# toolbox.net
KiCad netlist of a schematic drawn in EAGLE
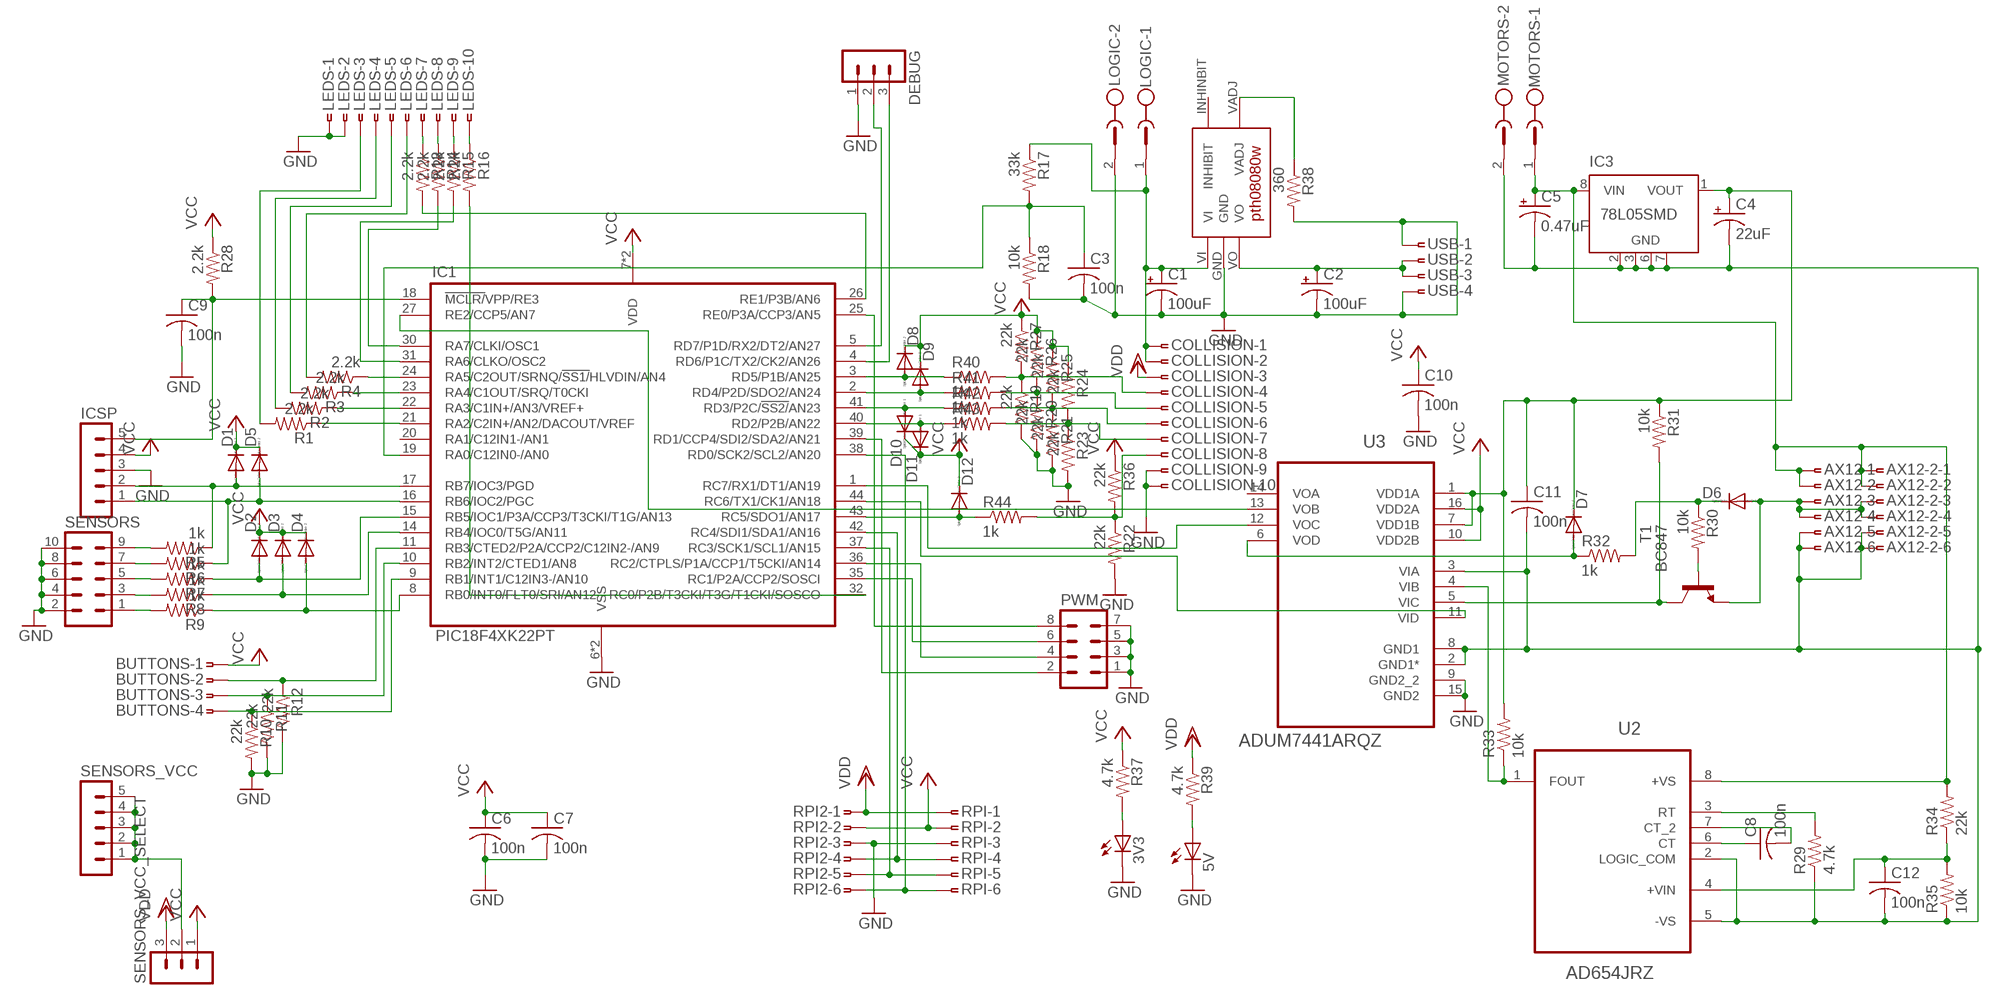
[diagram p0: schematic, sheet 1]

(export (version "E")
  (design (tool "Eeschema 10.0.6"))
  (components
    (comp (ref "3V3")
      (value "LEDCHIPLED_0805")
      (footprint "eagle-import:CHIPLED_0805")
      (libsource (lib "eagle-import") (part "LEDCHIPLED_0805"))
    )
    (comp (ref "5V")
      (value "LEDCHIPLED_0805")
      (footprint "eagle-import:CHIPLED_0805")
      (libsource (lib "eagle-import") (part "LEDCHIPLED_0805"))
    )
    (comp (ref "AX12")
      (value "SMDTOP-6")
      (footprint "eagle-import:SMDTOP6")
      (libsource (lib "eagle-import") (part "SMDTOP-6"))
    )
    (comp (ref "AX12-2")
      (value "SMDTOP-6")
      (footprint "eagle-import:SMDTOP6")
      (libsource (lib "eagle-import") (part "SMDTOP-6"))
    )
    (comp (ref "BUTTONS")
      (value "SMDTOP-4")
      (footprint "eagle-import:SMDTOP4")
      (libsource (lib "eagle-import") (part "SMDTOP-4"))
    )
    (comp (ref "C1")
      (value "100uF")
      (footprint "eagle-import:E2,5-6E")
      (libsource (lib "eagle-import") (part "CPOL-USE2,5-6E"))
    )
    (comp (ref "C2")
      (value "100uF")
      (footprint "eagle-import:E2,5-6E")
      (libsource (lib "eagle-import") (part "CPOL-USE2,5-6E"))
    )
    (comp (ref "C3")
      (value "100n")
      (footprint "eagle-import:C0805")
      (libsource (lib "eagle-import") (part "C-USC0805"))
    )
    (comp (ref "C4")
      (value "22uF")
      (footprint "eagle-import:E2-5")
      (libsource (lib "eagle-import") (part "CPOL-USE2-5"))
    )
    (comp (ref "C5")
      (value "0.47uF")
      (footprint "eagle-import:E2-5")
      (libsource (lib "eagle-import") (part "CPOL-USE2-5"))
    )
    (comp (ref "C6")
      (value "100n")
      (footprint "eagle-import:C0805")
      (libsource (lib "eagle-import") (part "C-USC0805"))
    )
    (comp (ref "C7")
      (value "100n")
      (footprint "eagle-import:C0805")
      (libsource (lib "eagle-import") (part "C-USC0805"))
    )
    (comp (ref "C8")
      (value "100n")
      (footprint "eagle-import:C0805")
      (libsource (lib "eagle-import") (part "C-USC0805"))
    )
    (comp (ref "C9")
      (value "100n")
      (footprint "eagle-import:C0805")
      (libsource (lib "eagle-import") (part "C-USC0805"))
    )
    (comp (ref "C10")
      (value "100n")
      (footprint "eagle-import:C0805")
      (libsource (lib "eagle-import") (part "C-USC0805"))
    )
    (comp (ref "C11")
      (value "100n")
      (footprint "eagle-import:C0805")
      (libsource (lib "eagle-import") (part "C-USC0805"))
    )
    (comp (ref "C12")
      (value "100n")
      (footprint "eagle-import:C0805")
      (libsource (lib "eagle-import") (part "C-USC0805"))
    )
    (comp (ref "COLLISION")
      (value "SMDTOP-10")
      (footprint "eagle-import:SMDTOP10")
      (libsource (lib "eagle-import") (part "SMDTOP-10"))
    )
    (comp (ref "D1")
      (value "DIODE-SOD523")
      (footprint "eagle-import:SOD523")
      (libsource (lib "eagle-import") (part "DIODE-SOD523"))
    )
    (comp (ref "D2")
      (value "DIODE-SOD523")
      (footprint "eagle-import:SOD523")
      (libsource (lib "eagle-import") (part "DIODE-SOD523"))
    )
    (comp (ref "D3")
      (value "DIODE-SOD523")
      (footprint "eagle-import:SOD523")
      (libsource (lib "eagle-import") (part "DIODE-SOD523"))
    )
    (comp (ref "D4")
      (value "DIODE-SOD523")
      (footprint "eagle-import:SOD523")
      (libsource (lib "eagle-import") (part "DIODE-SOD523"))
    )
    (comp (ref "D5")
      (value "DIODE-SOD523")
      (footprint "eagle-import:SOD523")
      (libsource (lib "eagle-import") (part "DIODE-SOD523"))
    )
    (comp (ref "D6")
      (value "DIODE-SOD523")
      (footprint "eagle-import:SOD523")
      (libsource (lib "eagle-import") (part "DIODE-SOD523"))
    )
    (comp (ref "D7")
      (value "DIODE-SOD523")
      (footprint "eagle-import:SOD523")
      (libsource (lib "eagle-import") (part "DIODE-SOD523"))
    )
    (comp (ref "D8")
      (value "DIODE-SOD523")
      (footprint "eagle-import:SOD523")
      (libsource (lib "eagle-import") (part "DIODE-SOD523"))
    )
    (comp (ref "D9")
      (value "DIODE-SOD523")
      (footprint "eagle-import:SOD523")
      (libsource (lib "eagle-import") (part "DIODE-SOD523"))
    )
    (comp (ref "D10")
      (value "DIODE-SOD523")
      (footprint "eagle-import:SOD523")
      (libsource (lib "eagle-import") (part "DIODE-SOD523"))
    )
    (comp (ref "D11")
      (value "DIODE-SOD523")
      (footprint "eagle-import:SOD523")
      (libsource (lib "eagle-import") (part "DIODE-SOD523"))
    )
    (comp (ref "D12")
      (value "DIODE-SOD523")
      (footprint "eagle-import:SOD523")
      (libsource (lib "eagle-import") (part "DIODE-SOD523"))
    )
    (comp (ref "DEBUG")
      (value "MA03-1")
      (footprint "eagle-import:MA03-1")
      (libsource (lib "eagle-import") (part "MA03-1"))
    )
    (comp (ref "IC1")
      (value "PIC18F4XK22PT")
      (footprint "eagle-import:TQFP44")
      (libsource (lib "eagle-import") (part "PIC18F4XK22PT"))
    )
    (comp (ref "IC3")
      (value "78L05SMD")
      (footprint "eagle-import:SO08")
      (libsource (lib "eagle-import") (part "78LSMD05"))
    )
    (comp (ref "ICSP")
      (value "MA05-1")
      (footprint "eagle-import:MA05-1")
      (libsource (lib "eagle-import") (part "MA05-1"))
    )
    (comp (ref "LEDS")
      (value "SMDTOP-10")
      (footprint "eagle-import:SMDTOP10")
      (libsource (lib "eagle-import") (part "SMDTOP-10"))
    )
    (comp (ref "LOGIC")
      (value "MSTBV2")
      (footprint "eagle-import:MSTBV2")
      (libsource (lib "eagle-import") (part "MSTBV2"))
    )
    (comp (ref "MOTORS")
      (value "MSTBV2")
      (footprint "eagle-import:MSTBV2")
      (libsource (lib "eagle-import") (part "MSTBV2"))
    )
    (comp (ref "PWM")
      (value "MA04-2")
      (footprint "eagle-import:MA04-2")
      (libsource (lib "eagle-import") (part "MA04-2"))
    )
    (comp (ref "R1")
      (value "2.2k")
      (footprint "eagle-import:M0805")
      (libsource (lib "eagle-import") (part "R-US_M0805"))
    )
    (comp (ref "R2")
      (value "2.2k")
      (footprint "eagle-import:M0805")
      (libsource (lib "eagle-import") (part "R-US_M0805"))
    )
    (comp (ref "R3")
      (value "2.2k")
      (footprint "eagle-import:M0805")
      (libsource (lib "eagle-import") (part "R-US_M0805"))
    )
    (comp (ref "R4")
      (value "2.2k")
      (footprint "eagle-import:M0805")
      (libsource (lib "eagle-import") (part "R-US_M0805"))
    )
    (comp (ref "R5")
      (value "1k")
      (footprint "eagle-import:M0805")
      (libsource (lib "eagle-import") (part "R-US_M0805"))
    )
    (comp (ref "R6")
      (value "1k")
      (footprint "eagle-import:M0805")
      (libsource (lib "eagle-import") (part "R-US_M0805"))
    )
    (comp (ref "R7")
      (value "1k")
      (footprint "eagle-import:M0805")
      (libsource (lib "eagle-import") (part "R-US_M0805"))
    )
    (comp (ref "R8")
      (value "1k")
      (footprint "eagle-import:M0805")
      (libsource (lib "eagle-import") (part "R-US_M0805"))
    )
    (comp (ref "R9")
      (value "1k")
      (footprint "eagle-import:M0805")
      (libsource (lib "eagle-import") (part "R-US_M0805"))
    )
    (comp (ref "R10")
      (value "22k")
      (footprint "eagle-import:M0805")
      (libsource (lib "eagle-import") (part "R-US_M0805"))
    )
    (comp (ref "R11")
      (value "22k")
      (footprint "eagle-import:M0805")
      (libsource (lib "eagle-import") (part "R-US_M0805"))
    )
    (comp (ref "R12")
      (value "22k")
      (footprint "eagle-import:M0805")
      (libsource (lib "eagle-import") (part "R-US_M0805"))
    )
    (comp (ref "R13")
      (value "2.2k")
      (footprint "eagle-import:M0805")
      (libsource (lib "eagle-import") (part "R-US_M0805"))
    )
    (comp (ref "R14")
      (value "2.2k")
      (footprint "eagle-import:M0805")
      (libsource (lib "eagle-import") (part "R-US_M0805"))
    )
    (comp (ref "R15")
      (value "2.2k")
      (footprint "eagle-import:M0805")
      (libsource (lib "eagle-import") (part "R-US_M0805"))
    )
    (comp (ref "R16")
      (value "2.2k")
      (footprint "eagle-import:M0805")
      (libsource (lib "eagle-import") (part "R-US_M0805"))
    )
    (comp (ref "R17")
      (value "33k")
      (footprint "eagle-import:M0805")
      (libsource (lib "eagle-import") (part "R-US_M0805"))
    )
    (comp (ref "R18")
      (value "10k")
      (footprint "eagle-import:M0805")
      (libsource (lib "eagle-import") (part "R-US_M0805"))
    )
    (comp (ref "R19")
      (value "22k")
      (footprint "eagle-import:M0805")
      (libsource (lib "eagle-import") (part "R-US_M0805"))
    )
    (comp (ref "R20")
      (value "22k")
      (footprint "eagle-import:M0805")
      (libsource (lib "eagle-import") (part "R-US_M0805"))
    )
    (comp (ref "R21")
      (value "22k")
      (footprint "eagle-import:M0805")
      (libsource (lib "eagle-import") (part "R-US_M0805"))
    )
    (comp (ref "R22")
      (value "22k")
      (footprint "eagle-import:M0805")
      (libsource (lib "eagle-import") (part "R-US_M0805"))
    )
    (comp (ref "R23")
      (value "22k")
      (footprint "eagle-import:M0805")
      (libsource (lib "eagle-import") (part "R-US_M0805"))
    )
    (comp (ref "R24")
      (value "22k")
      (footprint "eagle-import:M0805")
      (libsource (lib "eagle-import") (part "R-US_M0805"))
    )
    (comp (ref "R25")
      (value "22k")
      (footprint "eagle-import:M0805")
      (libsource (lib "eagle-import") (part "R-US_M0805"))
    )
    (comp (ref "R26")
      (value "22k")
      (footprint "eagle-import:M0805")
      (libsource (lib "eagle-import") (part "R-US_M0805"))
    )
    (comp (ref "R27")
      (value "22k")
      (footprint "eagle-import:M0805")
      (libsource (lib "eagle-import") (part "R-US_M0805"))
    )
    (comp (ref "R28")
      (value "2.2k")
      (footprint "eagle-import:M0805")
      (libsource (lib "eagle-import") (part "R-US_M0805"))
    )
    (comp (ref "R29")
      (value "4.7k")
      (footprint "eagle-import:M0805")
      (libsource (lib "eagle-import") (part "R-US_M0805"))
    )
    (comp (ref "R30")
      (value "10k")
      (footprint "eagle-import:M0805")
      (libsource (lib "eagle-import") (part "R-US_M0805"))
    )
    (comp (ref "R31")
      (value "10k")
      (footprint "eagle-import:M0805")
      (libsource (lib "eagle-import") (part "R-US_M0805"))
    )
    (comp (ref "R32")
      (value "1k")
      (footprint "eagle-import:M0805")
      (libsource (lib "eagle-import") (part "R-US_M0805"))
    )
    (comp (ref "R33")
      (value "10k")
      (footprint "eagle-import:M0805")
      (libsource (lib "eagle-import") (part "R-US_M0805"))
    )
    (comp (ref "R34")
      (value "22k")
      (footprint "eagle-import:M0805")
      (libsource (lib "eagle-import") (part "R-US_M0805"))
    )
    (comp (ref "R35")
      (value "10k")
      (footprint "eagle-import:M0805")
      (libsource (lib "eagle-import") (part "R-US_M0805"))
    )
    (comp (ref "R36")
      (value "22k")
      (footprint "eagle-import:M0805")
      (libsource (lib "eagle-import") (part "R-US_M0805"))
    )
    (comp (ref "R37")
      (value "4.7k")
      (footprint "eagle-import:M0805")
      (libsource (lib "eagle-import") (part "R-US_M0805"))
    )
    (comp (ref "R38")
      (value "360")
      (footprint "eagle-import:M0805")
      (libsource (lib "eagle-import") (part "R-US_M0805"))
    )
    (comp (ref "R39")
      (value "4.7k")
      (footprint "eagle-import:M0805")
      (libsource (lib "eagle-import") (part "R-US_M0805"))
    )
    (comp (ref "R40")
      (value "1k")
      (footprint "eagle-import:M0805")
      (libsource (lib "eagle-import") (part "R-US_M0805"))
    )
    (comp (ref "R41")
      (value "1k")
      (footprint "eagle-import:M0805")
      (libsource (lib "eagle-import") (part "R-US_M0805"))
    )
    (comp (ref "R42")
      (value "1k")
      (footprint "eagle-import:M0805")
      (libsource (lib "eagle-import") (part "R-US_M0805"))
    )
    (comp (ref "R43")
      (value "1k")
      (footprint "eagle-import:M0805")
      (libsource (lib "eagle-import") (part "R-US_M0805"))
    )
    (comp (ref "R44")
      (value "1k")
      (footprint "eagle-import:M0805")
      (libsource (lib "eagle-import") (part "R-US_M0805"))
    )
    (comp (ref "RPI")
      (value "SMDTOP-6")
      (footprint "eagle-import:SMDTOP6")
      (libsource (lib "eagle-import") (part "SMDTOP-6"))
    )
    (comp (ref "RPI2")
      (value "SMDTOP-6")
      (footprint "eagle-import:SMDTOP6")
      (libsource (lib "eagle-import") (part "SMDTOP-6"))
    )
    (comp (ref "SENSORS")
      (value "MA05-2")
      (footprint "eagle-import:MA05-2")
      (libsource (lib "eagle-import") (part "MA05-2"))
    )
    (comp (ref "SENSORS_VCC")
      (value "MA05-1")
      (footprint "eagle-import:MA05-1")
      (libsource (lib "eagle-import") (part "MA05-1"))
    )
    (comp (ref "SENSORS_VCC_SELECT")
      (value "MA03-1")
      (footprint "eagle-import:MA03-1")
      (libsource (lib "eagle-import") (part "MA03-1"))
    )
    (comp (ref "T1")
      (value "BC847")
      (footprint "eagle-import:SOT23")
      (libsource (lib "eagle-import") (part "BC847"))
    )
    (comp (ref "U$1")
      (value "REGUL_PTH")
      (footprint "eagle-import:REGUL_PTH")
      (libsource (lib "eagle-import") (part "REGUL_PTH"))
    )
    (comp (ref "U2")
      (value "AD654JRZ")
      (footprint "eagle-import:SOIC127P600X175-8N")
      (libsource (lib "eagle-import") (part "AD654JRZ"))
    )
    (comp (ref "U3")
      (value "ADUM7441ARQZ")
      (footprint "eagle-import:SOP64P600X175-16N")
      (libsource (lib "eagle-import") (part "ADUM7441ARQZ"))
    )
    (comp (ref "USB")
      (value "SMDTOP-4")
      (footprint "eagle-import:SMDTOP4")
      (libsource (lib "eagle-import") (part "SMDTOP-4"))
    )
  )
  (nets
    (net (code "1") (name "GND") (class "Default")
      (node (ref "3V3") (pin "C") (pinfunction "C_C") (pintype "passive"))
      (node (ref "5V") (pin "C") (pinfunction "C_C") (pintype "passive"))
      (node (ref "C1") (pin "-") (pinfunction "-_-") (pintype "passive"))
      (node (ref "C10") (pin "2") (pinfunction "2_2") (pintype "passive"))
      (node (ref "C2") (pin "-") (pinfunction "-_-") (pintype "passive"))
      (node (ref "C3") (pin "2") (pinfunction "2_2") (pintype "passive"))
      (node (ref "C6") (pin "2") (pinfunction "2_2") (pintype "passive"))
      (node (ref "C7") (pin "2") (pinfunction "2_2") (pintype "passive"))
      (node (ref "C9") (pin "2") (pinfunction "2_2") (pintype "passive"))
      (node (ref "COLLISION") (pin "10") (pinfunction "1_10") (pintype "passive"))
      (node (ref "COLLISION") (pin "9") (pinfunction "1_9") (pintype "passive"))
      (node (ref "DEBUG") (pin "1") (pinfunction "1_1") (pintype "passive"))
      (node (ref "IC1") (pin "29") (pinfunction "VSS_29") (pintype "power_in"))
      (node (ref "IC1") (pin "6") (pinfunction "VSS_6") (pintype "power_in"))
      (node (ref "ICSP") (pin "3") (pinfunction "3_3") (pintype "passive"))
      (node (ref "LEDS") (pin "1") (pinfunction "1_1") (pintype "passive"))
      (node (ref "LEDS") (pin "2") (pinfunction "1_2") (pintype "passive"))
      (node (ref "LOGIC") (pin "2") (pinfunction "SK_2") (pintype "passive"))
      (node (ref "PWM") (pin "1") (pinfunction "1_1") (pintype "passive"))
      (node (ref "PWM") (pin "3") (pinfunction "3_3") (pintype "passive"))
      (node (ref "PWM") (pin "5") (pinfunction "5_5") (pintype "passive"))
      (node (ref "PWM") (pin "7") (pinfunction "7_7") (pintype "passive"))
      (node (ref "R10") (pin "2") (pinfunction "2_2") (pintype "passive"))
      (node (ref "R11") (pin "2") (pinfunction "2_2") (pintype "passive"))
      (node (ref "R12") (pin "2") (pinfunction "2_2") (pintype "passive"))
      (node (ref "R18") (pin "2") (pinfunction "2_2") (pintype "passive"))
      (node (ref "R19") (pin "2") (pinfunction "2_2") (pintype "passive"))
      (node (ref "R20") (pin "2") (pinfunction "2_2") (pintype "passive"))
      (node (ref "R21") (pin "2") (pinfunction "2_2") (pintype "passive"))
      (node (ref "R22") (pin "2") (pinfunction "2_2") (pintype "passive"))
      (node (ref "R23") (pin "2") (pinfunction "2_2") (pintype "passive"))
      (node (ref "R38") (pin "2") (pinfunction "2_2") (pintype "passive"))
      (node (ref "RPI") (pin "3") (pinfunction "1_3") (pintype "passive"))
      (node (ref "RPI2") (pin "3") (pinfunction "1_3") (pintype "passive"))
      (node (ref "SENSORS") (pin "10") (pinfunction "10_10") (pintype "passive"))
      (node (ref "SENSORS") (pin "2") (pinfunction "2_2") (pintype "passive"))
      (node (ref "SENSORS") (pin "4") (pinfunction "4_4") (pintype "passive"))
      (node (ref "SENSORS") (pin "6") (pinfunction "6_6") (pintype "passive"))
      (node (ref "SENSORS") (pin "8") (pinfunction "8_8") (pintype "passive"))
      (node (ref "U$1") (pin "GND") (pinfunction "GND_GND") (pintype "bidirectional"))
      (node (ref "U3") (pin "15") (pinfunction "GND2_15") (pintype "passive"))
      (node (ref "U3") (pin "9") (pinfunction "GND2_2_9") (pintype "passive"))
      (node (ref "USB") (pin "1") (pinfunction "1_1") (pintype "passive"))
      (node (ref "USB") (pin "4") (pinfunction "1_4") (pintype "passive"))
    )
    (net (code "2") (name "Net-(3V3-PadA)") (class "Default")
      (node (ref "3V3") (pin "A") (pinfunction "A_A") (pintype "passive"))
      (node (ref "R37") (pin "2") (pinfunction "2_2") (pintype "passive"))
    )
    (net (code "3") (name "Net-(5V-PadA)") (class "Default")
      (node (ref "5V") (pin "A") (pinfunction "A_A") (pintype "passive"))
      (node (ref "R39") (pin "2") (pinfunction "2_2") (pintype "passive"))
    )
    (net (code "4") (name "Net-(AX12-2B-1)") (class "Default")
      (node (ref "AX12") (pin "1") (pinfunction "1_1") (pintype "passive"))
      (node (ref "AX12") (pin "2") (pinfunction "1_2") (pintype "passive"))
      (node (ref "AX12-2") (pin "1") (pinfunction "1_1") (pintype "passive"))
      (node (ref "AX12-2") (pin "2") (pinfunction "1_2") (pintype "passive"))
      (node (ref "C5") (pin "+") (pinfunction "+_+") (pintype "passive"))
      (node (ref "IC3") (pin "8") (pinfunction "VIN_8") (pintype "passive"))
      (node (ref "MOTORS") (pin "1") (pinfunction "SK_1") (pintype "passive"))
      (node (ref "R34") (pin "2") (pinfunction "2_2") (pintype "passive"))
      (node (ref "U2") (pin "8") (pinfunction "+VS_8") (pintype "power_in"))
    )
    (net (code "5") (name "Net-(AX12-2C-1)") (class "Default")
      (node (ref "AX12") (pin "3") (pinfunction "1_3") (pintype "passive"))
      (node (ref "AX12") (pin "4") (pinfunction "1_4") (pintype "passive"))
      (node (ref "AX12-2") (pin "3") (pinfunction "1_3") (pintype "passive"))
      (node (ref "AX12-2") (pin "4") (pinfunction "1_4") (pintype "passive"))
      (node (ref "D6") (pin "A") (pinfunction "A_A") (pintype "passive"))
      (node (ref "T1") (pin "2") (pinfunction "E_2") (pintype "passive"))
    )
    (net (code "6") (name "Net-(AX12-2E-1)") (class "Default")
      (node (ref "AX12") (pin "5") (pinfunction "1_5") (pintype "passive"))
      (node (ref "AX12") (pin "6") (pinfunction "1_6") (pintype "passive"))
      (node (ref "AX12-2") (pin "5") (pinfunction "1_5") (pintype "passive"))
      (node (ref "AX12-2") (pin "6") (pinfunction "1_6") (pintype "passive"))
      (node (ref "C11") (pin "2") (pinfunction "2_2") (pintype "passive"))
      (node (ref "C12") (pin "2") (pinfunction "2_2") (pintype "passive"))
      (node (ref "C4") (pin "-") (pinfunction "-_-") (pintype "passive"))
      (node (ref "C5") (pin "-") (pinfunction "-_-") (pintype "passive"))
      (node (ref "IC3") (pin "2") (pinfunction "GND_2") (pintype "power_in"))
      (node (ref "IC3") (pin "3") (pinfunction "GND_3") (pintype "power_in"))
      (node (ref "IC3") (pin "6") (pinfunction "GND_6") (pintype "power_in"))
      (node (ref "IC3") (pin "7") (pinfunction "GND_7") (pintype "power_in"))
      (node (ref "MOTORS") (pin "2") (pinfunction "SK_2") (pintype "passive"))
      (node (ref "R29") (pin "1") (pinfunction "1_1") (pintype "passive"))
      (node (ref "R35") (pin "1") (pinfunction "1_1") (pintype "passive"))
      (node (ref "U2") (pin "2") (pinfunction "LOGIC_COM_2") (pintype "passive"))
      (node (ref "U2") (pin "5") (pinfunction "-VS_5") (pintype "power_in"))
      (node (ref "U3") (pin "2") (pinfunction "GND1*_2") (pintype "passive"))
      (node (ref "U3") (pin "3") (pinfunction "VIA_3") (pintype "input"))
      (node (ref "U3") (pin "8") (pinfunction "GND1_8") (pintype "passive"))
    )
    (net (code "7") (name "Net-(BUTTONSB-1)") (class "Default")
      (node (ref "BUTTONS") (pin "2") (pinfunction "1_2") (pintype "passive"))
      (node (ref "IC1") (pin "11") (pinfunction "RB3/CTED2/P2A/CCP2/C12IN2-/AN9_11") (pintype "bidirectional"))
      (node (ref "R12") (pin "1") (pinfunction "1_1") (pintype "passive"))
    )
    (net (code "8") (name "Net-(BUTTONSC-1)") (class "Default")
      (node (ref "BUTTONS") (pin "3") (pinfunction "1_3") (pintype "passive"))
      (node (ref "IC1") (pin "10") (pinfunction "RB2/INT2/CTED1/AN8_10") (pintype "bidirectional"))
      (node (ref "R11") (pin "1") (pinfunction "1_1") (pintype "passive"))
    )
    (net (code "9") (name "Net-(BUTTONSD-1)") (class "Default")
      (node (ref "BUTTONS") (pin "4") (pinfunction "1_4") (pintype "passive"))
      (node (ref "IC1") (pin "9") (pinfunction "RB1/INT1/C12IN3-/AN10_9") (pintype "bidirectional"))
      (node (ref "R10") (pin "1") (pinfunction "1_1") (pintype "passive"))
    )
    (net (code "10") (name "Net-(COLLISIONC-1)") (class "Default")
      (node (ref "C1") (pin "+") (pinfunction "+_+") (pintype "passive"))
      (node (ref "COLLISION") (pin "1") (pinfunction "1_1") (pintype "passive"))
      (node (ref "COLLISION") (pin "2") (pinfunction "1_2") (pintype "passive"))
      (node (ref "LOGIC") (pin "1") (pinfunction "SK_1") (pintype "passive"))
      (node (ref "R17") (pin "1") (pinfunction "1_1") (pintype "passive"))
      (node (ref "U$1") (pin "VI") (pinfunction "VI_VI") (pintype "bidirectional"))
    )
    (net (code "11") (name "Net-(COLLISIONE-1)") (class "Default")
      (node (ref "COLLISION") (pin "4") (pinfunction "1_4") (pintype "passive"))
      (node (ref "R19") (pin "1") (pinfunction "1_1") (pintype "passive"))
      (node (ref "R27") (pin "2") (pinfunction "2_2") (pintype "passive"))
      (node (ref "R40") (pin "2") (pinfunction "2_2") (pintype "passive"))
    )
    (net (code "12") (name "Net-(COLLISIONF-1)") (class "Default")
      (node (ref "COLLISION") (pin "5") (pinfunction "1_5") (pintype "passive"))
      (node (ref "R20") (pin "1") (pinfunction "1_1") (pintype "passive"))
      (node (ref "R26") (pin "2") (pinfunction "2_2") (pintype "passive"))
      (node (ref "R41") (pin "2") (pinfunction "2_2") (pintype "passive"))
    )
    (net (code "13") (name "Net-(COLLISIONG-1)") (class "Default")
      (node (ref "COLLISION") (pin "6") (pinfunction "1_6") (pintype "passive"))
      (node (ref "R21") (pin "1") (pinfunction "1_1") (pintype "passive"))
      (node (ref "R25") (pin "2") (pinfunction "2_2") (pintype "passive"))
      (node (ref "R42") (pin "2") (pinfunction "2_2") (pintype "passive"))
    )
    (net (code "14") (name "Net-(COLLISIONH-1)") (class "Default")
      (node (ref "COLLISION") (pin "7") (pinfunction "1_7") (pintype "passive"))
      (node (ref "R23") (pin "1") (pinfunction "1_1") (pintype "passive"))
      (node (ref "R24") (pin "2") (pinfunction "2_2") (pintype "passive"))
      (node (ref "R43") (pin "2") (pinfunction "2_2") (pintype "passive"))
    )
    (net (code "15") (name "Net-(COLLISIONI-1)") (class "Default")
      (node (ref "COLLISION") (pin "8") (pinfunction "1_8") (pintype "passive"))
      (node (ref "R22") (pin "1") (pinfunction "1_1") (pintype "passive"))
      (node (ref "R36") (pin "2") (pinfunction "2_2") (pintype "passive"))
      (node (ref "R44") (pin "2") (pinfunction "2_2") (pintype "passive"))
    )
    (net (code "16") (name "Net-(D6-PadC)") (class "Default")
      (node (ref "D6") (pin "C") (pinfunction "C_C") (pintype "passive"))
      (node (ref "R30") (pin "1") (pinfunction "1_1") (pintype "passive"))
      (node (ref "R32") (pin "2") (pinfunction "2_2") (pintype "passive"))
    )
    (net (code "17") (name "Net-(IC1-RA0{slash}C12IN0-{slash}AN0)") (class "Default")
      (node (ref "C3") (pin "1") (pinfunction "1_1") (pintype "passive"))
      (node (ref "IC1") (pin "19") (pinfunction "RA0/C12IN0-/AN0_19") (pintype "bidirectional"))
      (node (ref "R17") (pin "2") (pinfunction "2_2") (pintype "passive"))
      (node (ref "R18") (pin "1") (pinfunction "1_1") (pintype "passive"))
    )
    (net (code "18") (name "Net-(IC1-RA2{slash}C2IN+{slash}AN2{slash}DACOUT{slash}VREF)") (class "Default")
      (node (ref "IC1") (pin "21") (pinfunction "RA2/C2IN+/AN2/DACOUT/VREF_21") (pintype "bidirectional"))
      (node (ref "R1") (pin "1") (pinfunction "1_1") (pintype "passive"))
    )
    (net (code "19") (name "Net-(IC1-RA3{slash}C1IN+{slash}AN3{slash}VREF+)") (class "Default")
      (node (ref "IC1") (pin "22") (pinfunction "RA3/C1IN+/AN3/VREF+_22") (pintype "bidirectional"))
      (node (ref "R2") (pin "1") (pinfunction "1_1") (pintype "passive"))
    )
    (net (code "20") (name "Net-(IC1-RA4{slash}C1OUT{slash}SRQ{slash}T0CKI)") (class "Default")
      (node (ref "IC1") (pin "23") (pinfunction "RA4/C1OUT/SRQ/T0CKI_23") (pintype "bidirectional"))
      (node (ref "R3") (pin "1") (pinfunction "1_1") (pintype "passive"))
    )
    (net (code "21") (name "Net-(IC1-RA5{slash}C2OUT{slash}SRNQ{slash}~{SS1{slash}}HLVDIN{slash}AN4)") (class "Default")
      (node (ref "IC1") (pin "24") (pinfunction "RA5/C2OUT/SRNQ/~{SS1/}HLVDIN/AN4_24") (pintype "bidirectional"))
      (node (ref "R4") (pin "1") (pinfunction "1_1") (pintype "passive"))
    )
    (net (code "22") (name "Net-(IC1-RA6{slash}CLKO{slash}OSC2)") (class "Default")
      (node (ref "IC1") (pin "31") (pinfunction "RA6/CLKO/OSC2_31") (pintype "bidirectional"))
      (node (ref "R15") (pin "2") (pinfunction "2_2") (pintype "passive"))
    )
    (net (code "23") (name "Net-(IC1-RA7{slash}CLKI{slash}OSC1)") (class "Default")
      (node (ref "IC1") (pin "30") (pinfunction "RA7/CLKI/OSC1_30") (pintype "bidirectional"))
      (node (ref "R14") (pin "2") (pinfunction "2_2") (pintype "passive"))
    )
    (net (code "24") (name "Net-(IC1-RB0{slash}INT0{slash}FLT0{slash}SRI{slash}AN12)") (class "Default")
      (node (ref "D4") (pin "A") (pinfunction "A_A") (pintype "passive"))
      (node (ref "IC1") (pin "8") (pinfunction "RB0/INT0/FLT0/SRI/AN12_8") (pintype "bidirectional"))
      (node (ref "R9") (pin "1") (pinfunction "1_1") (pintype "passive"))
    )
    (net (code "25") (name "Net-(IC1-RB4{slash}IOC0{slash}T5G{slash}AN11)") (class "Default")
      (node (ref "D3") (pin "A") (pinfunction "A_A") (pintype "passive"))
      (node (ref "IC1") (pin "14") (pinfunction "RB4/IOC0/T5G/AN11_14") (pintype "bidirectional"))
      (node (ref "R8") (pin "1") (pinfunction "1_1") (pintype "passive"))
    )
    (net (code "26") (name "Net-(IC1-RB5{slash}IOC1{slash}P3A{slash}CCP3{slash}T3CKI{slash}T1G{slash}AN13)") (class "Default")
      (node (ref "D2") (pin "A") (pinfunction "A_A") (pintype "passive"))
      (node (ref "IC1") (pin "15") (pinfunction "RB5/IOC1/P3A/CCP3/T3CKI/T1G/AN13_15") (pintype "bidirectional"))
      (node (ref "R7") (pin "1") (pinfunction "1_1") (pintype "passive"))
    )
    (net (code "27") (name "Net-(IC1-RB6{slash}IOC2{slash}PGC)") (class "Default")
      (node (ref "D5") (pin "A") (pinfunction "A_A") (pintype "passive"))
      (node (ref "IC1") (pin "16") (pinfunction "RB6/IOC2/PGC_16") (pintype "bidirectional"))
      (node (ref "ICSP") (pin "1") (pinfunction "1_1") (pintype "passive"))
      (node (ref "R6") (pin "1") (pinfunction "1_1") (pintype "passive"))
    )
    (net (code "28") (name "Net-(IC1-RB7{slash}IOC3{slash}PGD)") (class "Default")
      (node (ref "D1") (pin "A") (pinfunction "A_A") (pintype "passive"))
      (node (ref "IC1") (pin "17") (pinfunction "RB7/IOC3/PGD_17") (pintype "bidirectional"))
      (node (ref "ICSP") (pin "2") (pinfunction "2_2") (pintype "passive"))
      (node (ref "R5") (pin "1") (pinfunction "1_1") (pintype "passive"))
    )
    (net (code "29") (name "Net-(IC1-RC0{slash}P2B{slash}T3CKI{slash}T3G{slash}T1CKI{slash}SOSCO)") (class "Default")
      (node (ref "IC1") (pin "32") (pinfunction "RC0/P2B/T3CKI/T3G/T1CKI/SOSCO_32") (pintype "bidirectional"))
      (node (ref "R16") (pin "2") (pinfunction "2_2") (pintype "passive"))
    )
    (net (code "30") (name "Net-(IC1-RC1{slash}P2A{slash}CCP2{slash}SOSCI)") (class "Default")
      (node (ref "IC1") (pin "35") (pinfunction "RC1/P2A/CCP2/SOSCI_35") (pintype "bidirectional"))
      (node (ref "PWM") (pin "6") (pinfunction "6_6") (pintype "passive"))
    )
    (net (code "31") (name "Net-(IC1-RC2{slash}CTPLS{slash}P1A{slash}CCP1{slash}T5CKI{slash}AN14)") (class "Default")
      (node (ref "IC1") (pin "36") (pinfunction "RC2/CTPLS/P1A/CCP1/T5CKI/AN14_36") (pintype "bidirectional"))
      (node (ref "PWM") (pin "4") (pinfunction "4_4") (pintype "passive"))
    )
    (net (code "32") (name "Net-(IC1-RC3{slash}SCK1{slash}SCL1{slash}AN15)") (class "Default")
      (node (ref "IC1") (pin "37") (pinfunction "RC3/SCK1/SCL1/AN15_37") (pintype "bidirectional"))
      (node (ref "RPI") (pin "5") (pinfunction "1_5") (pintype "passive"))
      (node (ref "RPI2") (pin "5") (pinfunction "1_5") (pintype "passive"))
    )
    (net (code "33") (name "Net-(IC1-RC4{slash}SDI1{slash}SDA1{slash}AN16)") (class "Default")
      (node (ref "IC1") (pin "42") (pinfunction "RC4/SDI1/SDA1/AN16_42") (pintype "bidirectional"))
      (node (ref "RPI") (pin "4") (pinfunction "1_4") (pintype "passive"))
      (node (ref "RPI2") (pin "4") (pinfunction "1_4") (pintype "passive"))
    )
    (net (code "34") (name "Net-(IC1-RC5{slash}SDO1{slash}AN17)") (class "Default")
      (node (ref "D12") (pin "A") (pinfunction "A_A") (pintype "passive"))
      (node (ref "IC1") (pin "43") (pinfunction "RC5/SDO1/AN17_43") (pintype "bidirectional"))
      (node (ref "R44") (pin "1") (pinfunction "1_1") (pintype "passive"))
    )
    (net (code "35") (name "Net-(IC1-RC6{slash}TX1{slash}CK1{slash}AN18)") (class "Default")
      (node (ref "IC1") (pin "44") (pinfunction "RC6/TX1/CK1/AN18_44") (pintype "bidirectional"))
      (node (ref "U3") (pin "11") (pinfunction "VID_11") (pintype "input"))
    )
    (net (code "36") (name "Net-(IC1-RC7{slash}RX1{slash}DT1{slash}AN19)") (class "Default")
      (node (ref "IC1") (pin "1") (pinfunction "RC7/RX1/DT1/AN19_1") (pintype "bidirectional"))
      (node (ref "U3") (pin "12") (pinfunction "VOC_12") (pintype "output"))
    )
    (net (code "37") (name "Net-(IC1-RD0{slash}SCK2{slash}SCL2{slash}AN20)") (class "Default")
      (node (ref "IC1") (pin "38") (pinfunction "RD0/SCK2/SCL2/AN20_38") (pintype "bidirectional"))
      (node (ref "RPI") (pin "6") (pinfunction "1_6") (pintype "passive"))
      (node (ref "RPI2") (pin "6") (pinfunction "1_6") (pintype "passive"))
    )
    (net (code "38") (name "Net-(IC1-RD1{slash}CCP4{slash}SDI2{slash}SDA2{slash}AN21)") (class "Default")
      (node (ref "IC1") (pin "39") (pinfunction "RD1/CCP4/SDI2/SDA2/AN21_39") (pintype "bidirectional"))
      (node (ref "PWM") (pin "2") (pinfunction "2_2") (pintype "passive"))
    )
    (net (code "39") (name "Net-(IC1-RD2{slash}P2B{slash}AN22)") (class "Default")
      (node (ref "D11") (pin "A") (pinfunction "A_A") (pintype "passive"))
      (node (ref "IC1") (pin "40") (pinfunction "RD2/P2B/AN22_40") (pintype "bidirectional"))
      (node (ref "R43") (pin "1") (pinfunction "1_1") (pintype "passive"))
    )
    (net (code "40") (name "Net-(IC1-RD3{slash}P2C{slash}~{SS2{slash}}AN23)") (class "Default")
      (node (ref "D10") (pin "A") (pinfunction "A_A") (pintype "passive"))
      (node (ref "IC1") (pin "41") (pinfunction "RD3/P2C/~{SS2/}AN23_41") (pintype "bidirectional"))
      (node (ref "R42") (pin "1") (pinfunction "1_1") (pintype "passive"))
    )
    (net (code "41") (name "Net-(IC1-RD4{slash}P2D{slash}SDO2{slash}AN24)") (class "Default")
      (node (ref "D9") (pin "A") (pinfunction "A_A") (pintype "passive"))
      (node (ref "IC1") (pin "2") (pinfunction "RD4/P2D/SDO2/AN24_2") (pintype "bidirectional"))
      (node (ref "R41") (pin "1") (pinfunction "1_1") (pintype "passive"))
    )
    (net (code "42") (name "Net-(IC1-RD5{slash}P1B{slash}AN25)") (class "Default")
      (node (ref "D8") (pin "A") (pinfunction "A_A") (pintype "passive"))
      (node (ref "IC1") (pin "3") (pinfunction "RD5/P1B/AN25_3") (pintype "bidirectional"))
      (node (ref "R40") (pin "1") (pinfunction "1_1") (pintype "passive"))
    )
    (net (code "43") (name "Net-(IC1-RD6{slash}P1C{slash}TX2{slash}CK2{slash}AN26)") (class "Default")
      (node (ref "DEBUG") (pin "3") (pinfunction "3_3") (pintype "passive"))
      (node (ref "IC1") (pin "4") (pinfunction "RD6/P1C/TX2/CK2/AN26_4") (pintype "bidirectional"))
    )
    (net (code "44") (name "Net-(IC1-RD7{slash}P1D{slash}RX2{slash}DT2{slash}AN27)") (class "Default")
      (node (ref "DEBUG") (pin "2") (pinfunction "2_2") (pintype "passive"))
      (node (ref "IC1") (pin "5") (pinfunction "RD7/P1D/RX2/DT2/AN27_5") (pintype "bidirectional"))
    )
    (net (code "45") (name "Net-(IC1-RE0{slash}P3A{slash}CCP3{slash}AN5)") (class "Default")
      (node (ref "IC1") (pin "25") (pinfunction "RE0/P3A/CCP3/AN5_25") (pintype "bidirectional"))
      (node (ref "PWM") (pin "8") (pinfunction "8_8") (pintype "passive"))
    )
    (net (code "46") (name "Net-(IC1-RE1{slash}P3B{slash}AN6)") (class "Default")
      (node (ref "IC1") (pin "26") (pinfunction "RE1/P3B/AN6_26") (pintype "bidirectional"))
      (node (ref "R13") (pin "2") (pinfunction "2_2") (pintype "passive"))
    )
    (net (code "47") (name "Net-(IC1-RE2{slash}CCP5{slash}AN7)") (class "Default")
      (node (ref "IC1") (pin "27") (pinfunction "RE2/CCP5/AN7_27") (pintype "bidirectional"))
      (node (ref "U3") (pin "13") (pinfunction "VOB_13") (pintype "output"))
    )
    (net (code "48") (name "Net-(IC1-~{MCLR{slash}}VPP{slash}RE3)") (class "Default")
      (node (ref "C9") (pin "1") (pinfunction "1_1") (pintype "passive"))
      (node (ref "IC1") (pin "18") (pinfunction "~{MCLR/}VPP/RE3_18") (pintype "input"))
      (node (ref "ICSP") (pin "5") (pinfunction "5_5") (pintype "passive"))
      (node (ref "R28") (pin "2") (pinfunction "2_2") (pintype "passive"))
    )
    (net (code "49") (name "Net-(IC3A-VOUT)") (class "Default")
      (node (ref "C11") (pin "1") (pinfunction "1_1") (pintype "passive"))
      (node (ref "C4") (pin "+") (pinfunction "+_+") (pintype "passive"))
      (node (ref "D7") (pin "C") (pinfunction "C_C") (pintype "passive"))
      (node (ref "IC3") (pin "1") (pinfunction "VOUT_1") (pintype "output"))
      (node (ref "R31") (pin "1") (pinfunction "1_1") (pintype "passive"))
      (node (ref "R33") (pin "2") (pinfunction "2_2") (pintype "passive"))
      (node (ref "U3") (pin "1") (pinfunction "VDD1A_1") (pintype "power_in"))
      (node (ref "U3") (pin "7") (pinfunction "VDD1B_7") (pintype "power_in"))
    )
    (net (code "50") (name "Net-(LEDSB-1)") (class "Default")
      (node (ref "LEDS") (pin "10") (pinfunction "1_10") (pintype "passive"))
      (node (ref "R16") (pin "1") (pinfunction "1_1") (pintype "passive"))
    )
    (net (code "51") (name "Net-(LEDSD-1)") (class "Default")
      (node (ref "LEDS") (pin "3") (pinfunction "1_3") (pintype "passive"))
      (node (ref "R1") (pin "2") (pinfunction "2_2") (pintype "passive"))
    )
    (net (code "52") (name "Net-(LEDSE-1)") (class "Default")
      (node (ref "LEDS") (pin "4") (pinfunction "1_4") (pintype "passive"))
      (node (ref "R2") (pin "2") (pinfunction "2_2") (pintype "passive"))
    )
    (net (code "53") (name "Net-(LEDSF-1)") (class "Default")
      (node (ref "LEDS") (pin "5") (pinfunction "1_5") (pintype "passive"))
      (node (ref "R3") (pin "2") (pinfunction "2_2") (pintype "passive"))
    )
    (net (code "54") (name "Net-(LEDSG-1)") (class "Default")
      (node (ref "LEDS") (pin "6") (pinfunction "1_6") (pintype "passive"))
      (node (ref "R4") (pin "2") (pinfunction "2_2") (pintype "passive"))
    )
    (net (code "55") (name "Net-(LEDSH-1)") (class "Default")
      (node (ref "LEDS") (pin "7") (pinfunction "1_7") (pintype "passive"))
      (node (ref "R13") (pin "1") (pinfunction "1_1") (pintype "passive"))
    )
    (net (code "56") (name "Net-(LEDSI-1)") (class "Default")
      (node (ref "LEDS") (pin "8") (pinfunction "1_8") (pintype "passive"))
      (node (ref "R14") (pin "1") (pinfunction "1_1") (pintype "passive"))
    )
    (net (code "57") (name "Net-(LEDSJ-1)") (class "Default")
      (node (ref "LEDS") (pin "9") (pinfunction "1_9") (pintype "passive"))
      (node (ref "R15") (pin "1") (pinfunction "1_1") (pintype "passive"))
    )
    (net (code "58") (name "Net-(R5-Pad2)") (class "Default")
      (node (ref "R5") (pin "2") (pinfunction "2_2") (pintype "passive"))
      (node (ref "SENSORS") (pin "9") (pinfunction "9_9") (pintype "passive"))
    )
    (net (code "59") (name "Net-(R6-Pad2)") (class "Default")
      (node (ref "R6") (pin "2") (pinfunction "2_2") (pintype "passive"))
      (node (ref "SENSORS") (pin "7") (pinfunction "7_7") (pintype "passive"))
    )
    (net (code "60") (name "Net-(R7-Pad2)") (class "Default")
      (node (ref "R7") (pin "2") (pinfunction "2_2") (pintype "passive"))
      (node (ref "SENSORS") (pin "5") (pinfunction "5_5") (pintype "passive"))
    )
    (net (code "61") (name "Net-(R8-Pad2)") (class "Default")
      (node (ref "R8") (pin "2") (pinfunction "2_2") (pintype "passive"))
      (node (ref "SENSORS") (pin "3") (pinfunction "3_3") (pintype "passive"))
    )
    (net (code "62") (name "Net-(R9-Pad2)") (class "Default")
      (node (ref "R9") (pin "2") (pinfunction "2_2") (pintype "passive"))
      (node (ref "SENSORS") (pin "1") (pinfunction "1_1") (pintype "passive"))
    )
    (net (code "63") (name "Net-(R38-Pad1)") (class "Default")
      (node (ref "R38") (pin "1") (pinfunction "1_1") (pintype "passive"))
      (node (ref "U$1") (pin "VADJ") (pinfunction "VADJ_VADJ") (pintype "bidirectional"))
    )
    (net (code "64") (name "Net-(SENSORS_VCC-Pad1)") (class "Default")
      (node (ref "SENSORS_VCC") (pin "1") (pinfunction "1_1") (pintype "passive"))
      (node (ref "SENSORS_VCC") (pin "2") (pinfunction "2_2") (pintype "passive"))
      (node (ref "SENSORS_VCC") (pin "3") (pinfunction "3_3") (pintype "passive"))
      (node (ref "SENSORS_VCC") (pin "4") (pinfunction "4_4") (pintype "passive"))
      (node (ref "SENSORS_VCC") (pin "5") (pinfunction "5_5") (pintype "passive"))
      (node (ref "SENSORS_VCC_SELECT") (pin "2") (pinfunction "2_2") (pintype "passive"))
    )
    (net (code "65") (name "Net-(T1-B)") (class "Default")
      (node (ref "R30") (pin "2") (pinfunction "2_2") (pintype "passive"))
      (node (ref "T1") (pin "1") (pinfunction "B_1") (pintype "passive"))
    )
    (net (code "66") (name "Net-(T1-C)") (class "Default")
      (node (ref "R31") (pin "2") (pinfunction "2_2") (pintype "passive"))
      (node (ref "T1") (pin "3") (pinfunction "C_3") (pintype "passive"))
      (node (ref "U3") (pin "5") (pinfunction "VIC_5") (pintype "input"))
    )
    (net (code "67") (name "Net-(U2-+VIN)") (class "Default")
      (node (ref "C12") (pin "1") (pinfunction "1_1") (pintype "passive"))
      (node (ref "R34") (pin "1") (pinfunction "1_1") (pintype "passive"))
      (node (ref "R35") (pin "2") (pinfunction "2_2") (pintype "passive"))
      (node (ref "U2") (pin "4") (pinfunction "+VIN_4") (pintype "input"))
    )
    (net (code "68") (name "Net-(U2-CT)") (class "Default")
      (node (ref "C8") (pin "1") (pinfunction "1_1") (pintype "passive"))
      (node (ref "U2") (pin "6") (pinfunction "CT_6") (pintype "passive"))
    )
    (net (code "69") (name "Net-(U2-CT_2)") (class "Default")
      (node (ref "C8") (pin "2") (pinfunction "2_2") (pintype "passive"))
      (node (ref "U2") (pin "7") (pinfunction "CT_2_7") (pintype "passive"))
    )
    (net (code "70") (name "Net-(U2-FOUT)") (class "Default")
      (node (ref "R33") (pin "1") (pinfunction "1_1") (pintype "passive"))
      (node (ref "U2") (pin "1") (pinfunction "FOUT_1") (pintype "output"))
      (node (ref "U3") (pin "4") (pinfunction "VIB_4") (pintype "input"))
    )
    (net (code "71") (name "Net-(U2-RT)") (class "Default")
      (node (ref "R29") (pin "2") (pinfunction "2_2") (pintype "passive"))
      (node (ref "U2") (pin "3") (pinfunction "RT_3") (pintype "passive"))
    )
    (net (code "72") (name "Net-(U3-VOD)") (class "Default")
      (node (ref "D7") (pin "A") (pinfunction "A_A") (pintype "passive"))
      (node (ref "R32") (pin "1") (pinfunction "1_1") (pintype "passive"))
      (node (ref "U3") (pin "6") (pinfunction "VOD_6") (pintype "output"))
    )
    (net (code "73") (name "Net-(USBB-1)") (class "Default")
      (node (ref "C2") (pin "+") (pinfunction "+_+") (pintype "passive"))
      (node (ref "U$1") (pin "VO") (pinfunction "VO_VO") (pintype "bidirectional"))
      (node (ref "USB") (pin "2") (pinfunction "1_2") (pintype "passive"))
      (node (ref "USB") (pin "3") (pinfunction "1_3") (pintype "passive"))
    )
    (net (code "74") (name "VCC") (class "Default")
      (node (ref "BUTTONS") (pin "1") (pinfunction "1_1") (pintype "passive"))
      (node (ref "C10") (pin "1") (pinfunction "1_1") (pintype "passive"))
      (node (ref "C6") (pin "1") (pinfunction "1_1") (pintype "passive"))
      (node (ref "C7") (pin "1") (pinfunction "1_1") (pintype "passive"))
      (node (ref "D1") (pin "C") (pinfunction "C_C") (pintype "passive"))
      (node (ref "D10") (pin "C") (pinfunction "C_C") (pintype "passive"))
      (node (ref "D11") (pin "C") (pinfunction "C_C") (pintype "passive"))
      (node (ref "D12") (pin "C") (pinfunction "C_C") (pintype "passive"))
      (node (ref "D2") (pin "C") (pinfunction "C_C") (pintype "passive"))
      (node (ref "D3") (pin "C") (pinfunction "C_C") (pintype "passive"))
      (node (ref "D4") (pin "C") (pinfunction "C_C") (pintype "passive"))
      (node (ref "D5") (pin "C") (pinfunction "C_C") (pintype "passive"))
      (node (ref "D8") (pin "C") (pinfunction "C_C") (pintype "passive"))
      (node (ref "D9") (pin "C") (pinfunction "C_C") (pintype "passive"))
      (node (ref "IC1") (pin "28") (pinfunction "VDD_28") (pintype "power_in"))
      (node (ref "IC1") (pin "7") (pinfunction "VDD_7") (pintype "power_in"))
      (node (ref "ICSP") (pin "4") (pinfunction "4_4") (pintype "passive"))
      (node (ref "R24") (pin "1") (pinfunction "1_1") (pintype "passive"))
      (node (ref "R25") (pin "1") (pinfunction "1_1") (pintype "passive"))
      (node (ref "R26") (pin "1") (pinfunction "1_1") (pintype "passive"))
      (node (ref "R27") (pin "1") (pinfunction "1_1") (pintype "passive"))
      (node (ref "R28") (pin "1") (pinfunction "1_1") (pintype "passive"))
      (node (ref "R36") (pin "1") (pinfunction "1_1") (pintype "passive"))
      (node (ref "R37") (pin "1") (pinfunction "1_1") (pintype "passive"))
      (node (ref "RPI") (pin "2") (pinfunction "1_2") (pintype "passive"))
      (node (ref "RPI2") (pin "2") (pinfunction "1_2") (pintype "passive"))
      (node (ref "SENSORS_VCC_SELECT") (pin "1") (pinfunction "1_1") (pintype "passive"))
      (node (ref "U3") (pin "10") (pinfunction "VDD2B_10") (pintype "power_in"))
      (node (ref "U3") (pin "16") (pinfunction "VDD2A_16") (pintype "power_in"))
    )
    (net (code "75") (name "VDD") (class "Default")
      (node (ref "COLLISION") (pin "3") (pinfunction "1_3") (pintype "passive"))
      (node (ref "R39") (pin "1") (pinfunction "1_1") (pintype "passive"))
      (node (ref "RPI") (pin "1") (pinfunction "1_1") (pintype "passive"))
      (node (ref "RPI2") (pin "1") (pinfunction "1_1") (pintype "passive"))
      (node (ref "SENSORS_VCC_SELECT") (pin "3") (pinfunction "3_3") (pintype "passive"))
    )
    (net (code "76") (name "unconnected-(IC1-RA1{slash}C12IN1-{slash}AN1-Pad20)") (class "Default")
      (node (ref "IC1") (pin "20") (pinfunction "RA1/C12IN1-/AN1_20") (pintype "bidirectional"))
    )
    (net (code "77") (name "unconnected-(U$1-INHIBIT-PadINHINBIT)") (class "Default")
      (node (ref "U$1") (pin "INHINBIT") (pinfunction "INHIBIT_INHINBIT") (pintype "bidirectional"))
    )
    (net (code "78") (name "unconnected-(U3-VOA-Pad14)") (class "Default")
      (node (ref "U3") (pin "14") (pinfunction "VOA_14") (pintype "output"))
    )
  )
)
